# hub_board.net
KiCad netlist of a schematic drawn in EAGLE
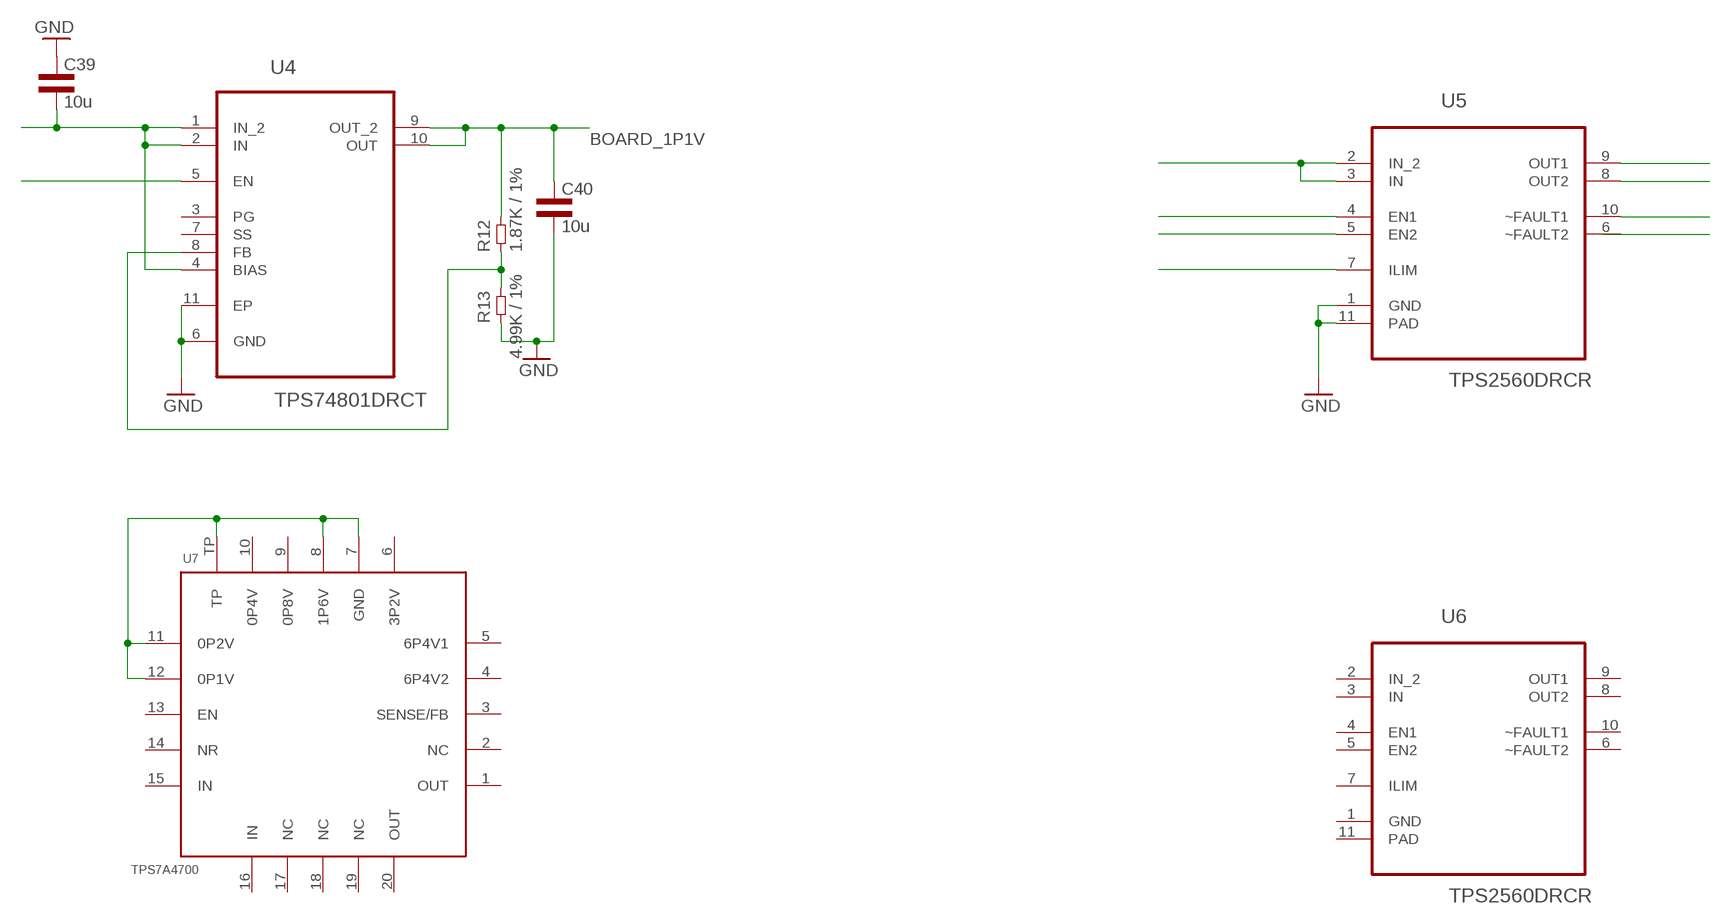
[diagram p0: schematic, sheet 1]
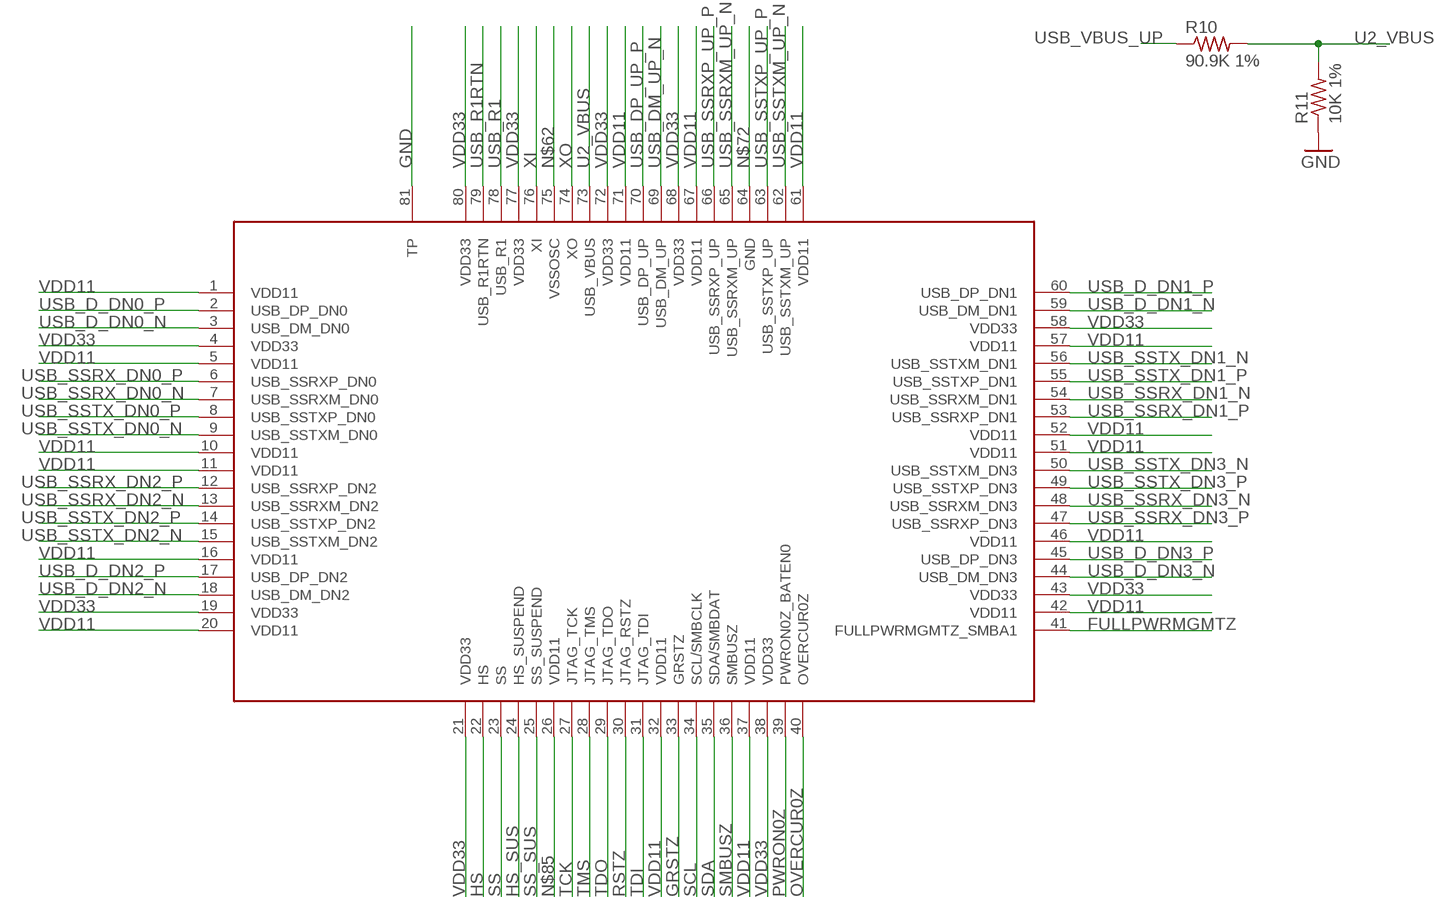
[diagram p1: schematic, sheet 2]
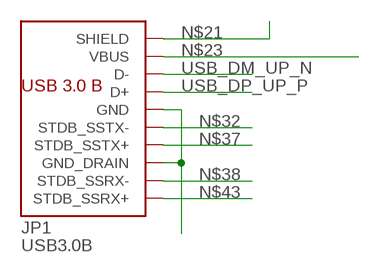
[diagram p2: schematic, sheet 3]
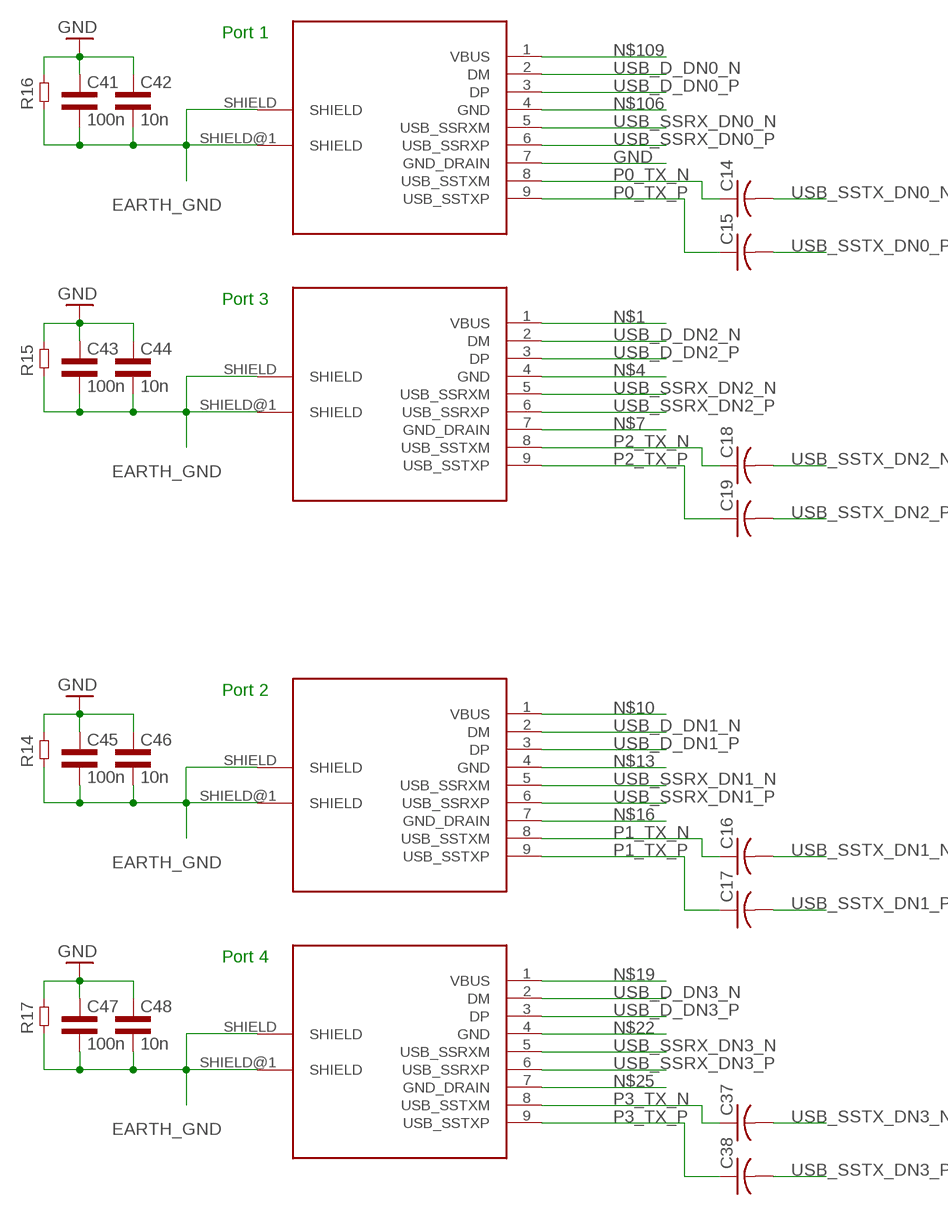
[diagram p3: schematic, sheet 4]
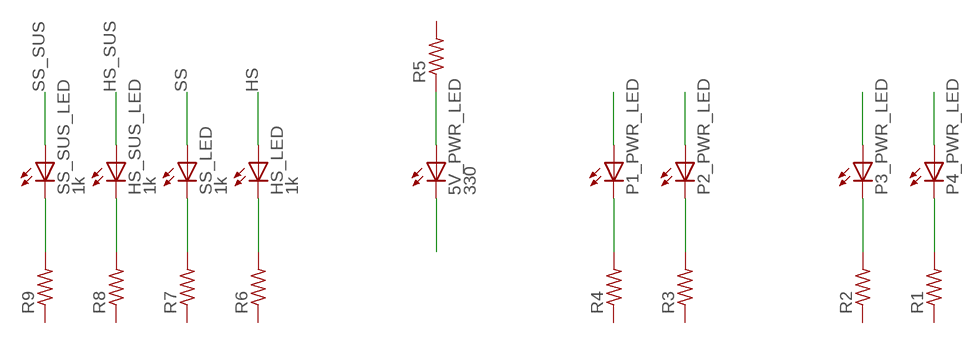
[diagram p4: schematic, sheet 5]
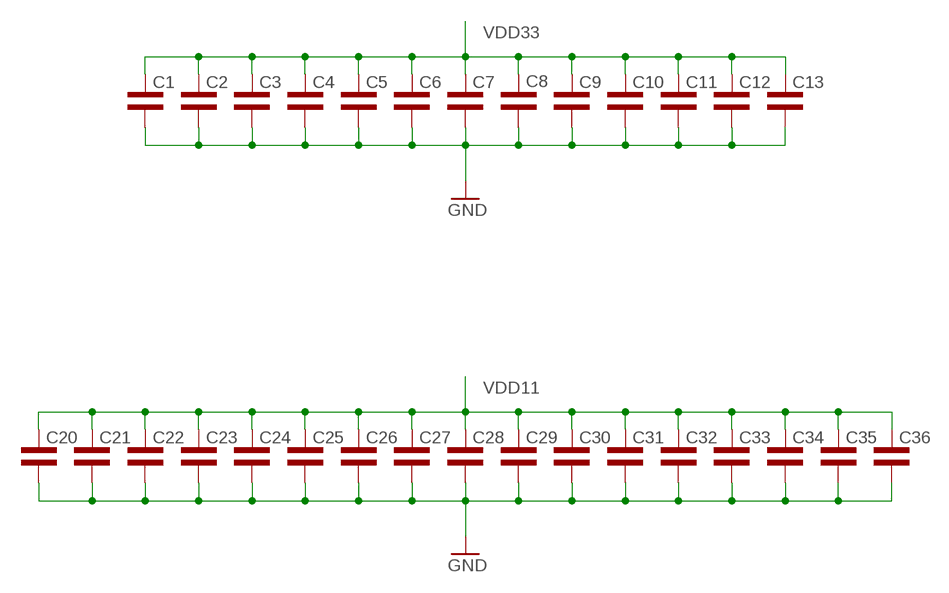
[diagram p5: schematic, sheet 6]

(export (version "E")
  (design (tool "Eeschema 10.0.6"))
  (components
    (comp (ref "C1")
      (value "CAP0402L3")
      (footprint "eagle-import:0402L3")
      (libsource (lib "eagle-import") (part "CAP0402L3"))
    )
    (comp (ref "C2")
      (value "CAP0402L3")
      (footprint "eagle-import:0402L3")
      (libsource (lib "eagle-import") (part "CAP0402L3"))
    )
    (comp (ref "C3")
      (value "CAP0402L3")
      (footprint "eagle-import:0402L3")
      (libsource (lib "eagle-import") (part "CAP0402L3"))
    )
    (comp (ref "C4")
      (value "CAP0402L3")
      (footprint "eagle-import:0402L3")
      (libsource (lib "eagle-import") (part "CAP0402L3"))
    )
    (comp (ref "C5")
      (value "CAP0402L3")
      (footprint "eagle-import:0402L3")
      (libsource (lib "eagle-import") (part "CAP0402L3"))
    )
    (comp (ref "C6")
      (value "CAP0402L3")
      (footprint "eagle-import:0402L3")
      (libsource (lib "eagle-import") (part "CAP0402L3"))
    )
    (comp (ref "C7")
      (value "CAP0402L3")
      (footprint "eagle-import:0402L3")
      (libsource (lib "eagle-import") (part "CAP0402L3"))
    )
    (comp (ref "C8")
      (value "CAP0402L3")
      (footprint "eagle-import:0402L3")
      (libsource (lib "eagle-import") (part "CAP0402L3"))
    )
    (comp (ref "C9")
      (value "CAP0402L3")
      (footprint "eagle-import:0402L3")
      (libsource (lib "eagle-import") (part "CAP0402L3"))
    )
    (comp (ref "C10")
      (value "CAP0402L3")
      (footprint "eagle-import:0402L3")
      (libsource (lib "eagle-import") (part "CAP0402L3"))
    )
    (comp (ref "C11")
      (value "CAP0402L3")
      (footprint "eagle-import:0402L3")
      (libsource (lib "eagle-import") (part "CAP0402L3"))
    )
    (comp (ref "C12")
      (value "CAP0402L3")
      (footprint "eagle-import:0402L3")
      (libsource (lib "eagle-import") (part "CAP0402L3"))
    )
    (comp (ref "C13")
      (value "CAP0402L3")
      (footprint "eagle-import:0402L3")
      (libsource (lib "eagle-import") (part "CAP0402L3"))
    )
    (comp (ref "C20")
      (value "CAP0402L3")
      (footprint "eagle-import:0402L3")
      (libsource (lib "eagle-import") (part "CAP0402L3"))
    )
    (comp (ref "C21")
      (value "CAP0402L3")
      (footprint "eagle-import:0402L3")
      (libsource (lib "eagle-import") (part "CAP0402L3"))
    )
    (comp (ref "C22")
      (value "CAP0402L3")
      (footprint "eagle-import:0402L3")
      (libsource (lib "eagle-import") (part "CAP0402L3"))
    )
    (comp (ref "C23")
      (value "CAP0402L3")
      (footprint "eagle-import:0402L3")
      (libsource (lib "eagle-import") (part "CAP0402L3"))
    )
    (comp (ref "C24")
      (value "CAP0402L3")
      (footprint "eagle-import:0402L3")
      (libsource (lib "eagle-import") (part "CAP0402L3"))
    )
    (comp (ref "C25")
      (value "CAP0402L3")
      (footprint "eagle-import:0402L3")
      (libsource (lib "eagle-import") (part "CAP0402L3"))
    )
    (comp (ref "C26")
      (value "CAP0402L3")
      (footprint "eagle-import:0402L3")
      (libsource (lib "eagle-import") (part "CAP0402L3"))
    )
    (comp (ref "C27")
      (value "CAP0402L3")
      (footprint "eagle-import:0402L3")
      (libsource (lib "eagle-import") (part "CAP0402L3"))
    )
    (comp (ref "C28")
      (value "CAP0402L3")
      (footprint "eagle-import:0402L3")
      (libsource (lib "eagle-import") (part "CAP0402L3"))
    )
    (comp (ref "C29")
      (value "CAP0402L3")
      (footprint "eagle-import:0402L3")
      (libsource (lib "eagle-import") (part "CAP0402L3"))
    )
    (comp (ref "C30")
      (value "CAP0402L3")
      (footprint "eagle-import:0402L3")
      (libsource (lib "eagle-import") (part "CAP0402L3"))
    )
    (comp (ref "C31")
      (value "CAP0402L3")
      (footprint "eagle-import:0402L3")
      (libsource (lib "eagle-import") (part "CAP0402L3"))
    )
    (comp (ref "C32")
      (value "CAP0402L3")
      (footprint "eagle-import:0402L3")
      (libsource (lib "eagle-import") (part "CAP0402L3"))
    )
    (comp (ref "C33")
      (value "CAP0402L3")
      (footprint "eagle-import:0402L3")
      (libsource (lib "eagle-import") (part "CAP0402L3"))
    )
    (comp (ref "C34")
      (value "CAP0402L3")
      (footprint "eagle-import:0402L3")
      (libsource (lib "eagle-import") (part "CAP0402L3"))
    )
    (comp (ref "C35")
      (value "CAP0402L3")
      (footprint "eagle-import:0402L3")
      (libsource (lib "eagle-import") (part "CAP0402L3"))
    )
    (comp (ref "C36")
      (value "CAP0402L3")
      (footprint "eagle-import:0402L3")
      (libsource (lib "eagle-import") (part "CAP0402L3"))
    )
    (comp (ref "JP1")
      (value "USB3.0B")
      (footprint "eagle-import:AMPHENOLUSB3.0B")
      (libsource (lib "eagle-import") (part "USB3.0B"))
    )
    (comp (ref "C39")
      (value "10u")
      (footprint "eagle-import:0805L3")
      (libsource (lib "eagle-import") (part "CAP0805L3"))
    )
    (comp (ref "C40")
      (value "10u")
      (footprint "eagle-import:0805L3")
      (libsource (lib "eagle-import") (part "CAP0805L3"))
    )
    (comp (ref "R12")
      (value "1.87K / 1%")
      (footprint "eagle-import:0603L3")
      (libsource (lib "eagle-import") (part "RES0603L3"))
    )
    (comp (ref "R13")
      (value "4.99K / 1%")
      (footprint "eagle-import:0603L3")
      (libsource (lib "eagle-import") (part "RES0603L3"))
    )
    (comp (ref "U4")
      (value "TPS74801DRCT")
      (footprint "eagle-import:SON50P300X300X100-11N")
      (libsource (lib "eagle-import") (part "TPS74801DRCT"))
    )
    (comp (ref "U5")
      (value "TPS2560DRCR")
      (footprint "eagle-import:SON50P300X300X100-11N")
      (libsource (lib "eagle-import") (part "TPS2560DRCR"))
    )
    (comp (ref "U6")
      (value "TPS2560DRCR")
      (footprint "eagle-import:SON50P300X300X100-11N")
      (libsource (lib "eagle-import") (part "TPS2560DRCR"))
    )
    (comp (ref "U7")
      (value "TPS7A4700")
      (footprint "eagle-import:VQFN-20")
      (libsource (lib "eagle-import") (part "TPS7A4700"))
    )
    (comp (ref "5V_PWR_LED")
      (value "330")
      (footprint "eagle-import:CHIP-LED0603")
      (libsource (lib "eagle-import") (part "LEDCHIP-LED0603"))
    )
    (comp (ref "HS_LED")
      (value "1k")
      (footprint "eagle-import:CHIP-LED0603")
      (libsource (lib "eagle-import") (part "LEDCHIP-LED0603"))
    )
    (comp (ref "HS_SUS_LED")
      (value "1k")
      (footprint "eagle-import:CHIP-LED0603")
      (libsource (lib "eagle-import") (part "LEDCHIP-LED0603"))
    )
    (comp (ref "P1_PWR_LED")
      (value "LEDCHIP-LED0603")
      (footprint "eagle-import:CHIP-LED0603")
      (libsource (lib "eagle-import") (part "LEDCHIP-LED0603"))
    )
    (comp (ref "P2_PWR_LED")
      (value "LEDCHIP-LED0603")
      (footprint "eagle-import:CHIP-LED0603")
      (libsource (lib "eagle-import") (part "LEDCHIP-LED0603"))
    )
    (comp (ref "P3_PWR_LED")
      (value "LEDCHIP-LED0603")
      (footprint "eagle-import:CHIP-LED0603")
      (libsource (lib "eagle-import") (part "LEDCHIP-LED0603"))
    )
    (comp (ref "P4_PWR_LED")
      (value "LEDCHIP-LED0603")
      (footprint "eagle-import:CHIP-LED0603")
      (libsource (lib "eagle-import") (part "LEDCHIP-LED0603"))
    )
    (comp (ref "R1")
      (value "R-US_R0603")
      (footprint "eagle-import:R0603")
      (libsource (lib "eagle-import") (part "R-US_R0603"))
    )
    (comp (ref "R2")
      (value "R-US_R0603")
      (footprint "eagle-import:R0603")
      (libsource (lib "eagle-import") (part "R-US_R0603"))
    )
    (comp (ref "R3")
      (value "R-US_R0603")
      (footprint "eagle-import:R0603")
      (libsource (lib "eagle-import") (part "R-US_R0603"))
    )
    (comp (ref "R4")
      (value "R-US_R0603")
      (footprint "eagle-import:R0603")
      (libsource (lib "eagle-import") (part "R-US_R0603"))
    )
    (comp (ref "R5")
      (value "R-US_R0603")
      (footprint "eagle-import:R0603")
      (libsource (lib "eagle-import") (part "R-US_R0603"))
    )
    (comp (ref "R6")
      (value "R-US_R0603")
      (footprint "eagle-import:R0603")
      (libsource (lib "eagle-import") (part "R-US_R0603"))
    )
    (comp (ref "R7")
      (value "R-US_R0603")
      (footprint "eagle-import:R0603")
      (libsource (lib "eagle-import") (part "R-US_R0603"))
    )
    (comp (ref "R8")
      (value "R-US_R0603")
      (footprint "eagle-import:R0603")
      (libsource (lib "eagle-import") (part "R-US_R0603"))
    )
    (comp (ref "R9")
      (value "R-US_R0603")
      (footprint "eagle-import:R0603")
      (libsource (lib "eagle-import") (part "R-US_R0603"))
    )
    (comp (ref "SS_LED")
      (value "1k")
      (footprint "eagle-import:CHIP-LED0603")
      (libsource (lib "eagle-import") (part "LEDCHIP-LED0603"))
    )
    (comp (ref "SS_SUS_LED")
      (value "1k")
      (footprint "eagle-import:CHIP-LED0603")
      (libsource (lib "eagle-import") (part "LEDCHIP-LED0603"))
    )
    (comp (ref "R10")
      (value "90.9K 1%")
      (footprint "eagle-import:R0603")
      (libsource (lib "eagle-import") (part "R-US_R0603"))
    )
    (comp (ref "R11")
      (value "10K 1%")
      (footprint "eagle-import:R0603")
      (libsource (lib "eagle-import") (part "R-US_R0603"))
    )
    (comp (ref "U2")
      (value "TUSB8040PFP")
      (footprint "eagle-import:S-PQFP-G80")
      (libsource (lib "eagle-import") (part "TUSB8040PFP"))
    )
    (comp (ref "C14")
      (value "C-USC0201")
      (footprint "eagle-import:C0201")
      (libsource (lib "eagle-import") (part "C-USC0201"))
    )
    (comp (ref "C15")
      (value "C-USC0201")
      (footprint "eagle-import:C0201")
      (libsource (lib "eagle-import") (part "C-USC0201"))
    )
    (comp (ref "C16")
      (value "C-USC0201")
      (footprint "eagle-import:C0201")
      (libsource (lib "eagle-import") (part "C-USC0201"))
    )
    (comp (ref "C17")
      (value "C-USC0201")
      (footprint "eagle-import:C0201")
      (libsource (lib "eagle-import") (part "C-USC0201"))
    )
    (comp (ref "C18")
      (value "C-USC0201")
      (footprint "eagle-import:C0201")
      (libsource (lib "eagle-import") (part "C-USC0201"))
    )
    (comp (ref "C19")
      (value "C-USC0201")
      (footprint "eagle-import:C0201")
      (libsource (lib "eagle-import") (part "C-USC0201"))
    )
    (comp (ref "C37")
      (value "C-USC0201")
      (footprint "eagle-import:C0201")
      (libsource (lib "eagle-import") (part "C-USC0201"))
    )
    (comp (ref "C38")
      (value "C-USC0201")
      (footprint "eagle-import:C0201")
      (libsource (lib "eagle-import") (part "C-USC0201"))
    )
    (comp (ref "C41")
      (value "100n")
      (footprint "eagle-import:0603L3")
      (libsource (lib "eagle-import") (part "CAP0603L3"))
    )
    (comp (ref "C42")
      (value "10n")
      (footprint "eagle-import:0603L3")
      (libsource (lib "eagle-import") (part "CAP0603L3"))
    )
    (comp (ref "C43")
      (value "100n")
      (footprint "eagle-import:0603L3")
      (libsource (lib "eagle-import") (part "CAP0603L3"))
    )
    (comp (ref "C44")
      (value "10n")
      (footprint "eagle-import:0603L3")
      (libsource (lib "eagle-import") (part "CAP0603L3"))
    )
    (comp (ref "C45")
      (value "100n")
      (footprint "eagle-import:0603L3")
      (libsource (lib "eagle-import") (part "CAP0603L3"))
    )
    (comp (ref "C46")
      (value "10n")
      (footprint "eagle-import:0603L3")
      (libsource (lib "eagle-import") (part "CAP0603L3"))
    )
    (comp (ref "C47")
      (value "100n")
      (footprint "eagle-import:0603L3")
      (libsource (lib "eagle-import") (part "CAP0603L3"))
    )
    (comp (ref "C48")
      (value "10n")
      (footprint "eagle-import:0603L3")
      (libsource (lib "eagle-import") (part "CAP0603L3"))
    )
    (comp (ref "R14")
      (value "RES0603L3")
      (footprint "eagle-import:0603L3")
      (libsource (lib "eagle-import") (part "RES0603L3"))
    )
    (comp (ref "R15")
      (value "RES0603L3")
      (footprint "eagle-import:0603L3")
      (libsource (lib "eagle-import") (part "RES0603L3"))
    )
    (comp (ref "R16")
      (value "RES0603L3")
      (footprint "eagle-import:0603L3")
      (libsource (lib "eagle-import") (part "RES0603L3"))
    )
    (comp (ref "R17")
      (value "RES0603L3")
      (footprint "eagle-import:0603L3")
      (libsource (lib "eagle-import") (part "RES0603L3"))
    )
    (comp (ref "U$1")
      (value "USB_SS_CONN_TYPE_A")
      (footprint "eagle-import:R_A_DIP")
      (libsource (lib "eagle-import") (part "USB_SS_CONN_TYPE_A"))
    )
    (comp (ref "U$3")
      (value "USB_SS_CONN_TYPE_A")
      (footprint "eagle-import:R_A_DIP")
      (libsource (lib "eagle-import") (part "USB_SS_CONN_TYPE_A"))
    )
    (comp (ref "U$4")
      (value "USB_SS_CONN_TYPE_A")
      (footprint "eagle-import:R_A_DIP")
      (libsource (lib "eagle-import") (part "USB_SS_CONN_TYPE_A"))
    )
    (comp (ref "U$5")
      (value "USB_SS_CONN_TYPE_A")
      (footprint "eagle-import:R_A_DIP")
      (libsource (lib "eagle-import") (part "USB_SS_CONN_TYPE_A"))
    )
  )
  (nets
    (net (code "1") (name "BOARD_1P1V") (class "Default")
      (node (ref "C40") (pin "1") (pinfunction "1_1") (pintype "bidirectional"))
      (node (ref "R12") (pin "P$2") (pinfunction "2_P$2") (pintype "bidirectional"))
      (node (ref "U4") (pin "10") (pinfunction "OUT_10") (pintype "output"))
      (node (ref "U4") (pin "9") (pinfunction "OUT_2_9") (pintype "output"))
    )
    (net (code "2") (name "EARTH_GND") (class "Default")
      (node (ref "C41") (pin "P$2") (pinfunction "2_P$2") (pintype "bidirectional"))
      (node (ref "C42") (pin "P$2") (pinfunction "2_P$2") (pintype "bidirectional"))
      (node (ref "C43") (pin "P$2") (pinfunction "2_P$2") (pintype "bidirectional"))
      (node (ref "C44") (pin "P$2") (pinfunction "2_P$2") (pintype "bidirectional"))
      (node (ref "C45") (pin "P$2") (pinfunction "2_P$2") (pintype "bidirectional"))
      (node (ref "C46") (pin "P$2") (pinfunction "2_P$2") (pintype "bidirectional"))
      (node (ref "C47") (pin "P$2") (pinfunction "2_P$2") (pintype "bidirectional"))
      (node (ref "C48") (pin "P$2") (pinfunction "2_P$2") (pintype "bidirectional"))
      (node (ref "R14") (pin "P$1") (pinfunction "1_P$1") (pintype "bidirectional"))
      (node (ref "R15") (pin "P$1") (pinfunction "1_P$1") (pintype "bidirectional"))
      (node (ref "R16") (pin "P$1") (pinfunction "1_P$1") (pintype "bidirectional"))
      (node (ref "R17") (pin "P$1") (pinfunction "1_P$1") (pintype "bidirectional"))
      (node (ref "U$1") (pin "SHIELD") (pinfunction "SHIELD_SHIELD") (pintype "bidirectional"))
      (node (ref "U$1") (pin "SHIELD@1") (pinfunction "SHIELD_SHIELD@1") (pintype "bidirectional"))
      (node (ref "U$3") (pin "SHIELD") (pinfunction "SHIELD_SHIELD") (pintype "bidirectional"))
      (node (ref "U$3") (pin "SHIELD@1") (pinfunction "SHIELD_SHIELD@1") (pintype "bidirectional"))
      (node (ref "U$4") (pin "SHIELD") (pinfunction "SHIELD_SHIELD") (pintype "bidirectional"))
      (node (ref "U$4") (pin "SHIELD@1") (pinfunction "SHIELD_SHIELD@1") (pintype "bidirectional"))
      (node (ref "U$5") (pin "SHIELD") (pinfunction "SHIELD_SHIELD") (pintype "bidirectional"))
      (node (ref "U$5") (pin "SHIELD@1") (pinfunction "SHIELD_SHIELD@1") (pintype "bidirectional"))
    )
    (net (code "3") (name "FULLPWRMGMTZ") (class "Default")
      (node (ref "U2") (pin "41") (pinfunction "FULLPWRMGMTZ_SMBA1_41") (pintype "bidirectional"))
    )
    (net (code "4") (name "GND") (class "Default")
      (node (ref "C1") (pin "P$2") (pinfunction "2_P$2") (pintype "bidirectional"))
      (node (ref "C10") (pin "P$2") (pinfunction "2_P$2") (pintype "bidirectional"))
      (node (ref "C11") (pin "P$2") (pinfunction "2_P$2") (pintype "bidirectional"))
      (node (ref "C12") (pin "P$2") (pinfunction "2_P$2") (pintype "bidirectional"))
      (node (ref "C13") (pin "P$2") (pinfunction "2_P$2") (pintype "bidirectional"))
      (node (ref "C2") (pin "P$2") (pinfunction "2_P$2") (pintype "bidirectional"))
      (node (ref "C20") (pin "P$2") (pinfunction "2_P$2") (pintype "bidirectional"))
      (node (ref "C21") (pin "P$2") (pinfunction "2_P$2") (pintype "bidirectional"))
      (node (ref "C22") (pin "P$2") (pinfunction "2_P$2") (pintype "bidirectional"))
      (node (ref "C23") (pin "P$2") (pinfunction "2_P$2") (pintype "bidirectional"))
      (node (ref "C24") (pin "P$2") (pinfunction "2_P$2") (pintype "bidirectional"))
      (node (ref "C25") (pin "P$2") (pinfunction "2_P$2") (pintype "bidirectional"))
      (node (ref "C26") (pin "P$2") (pinfunction "2_P$2") (pintype "bidirectional"))
      (node (ref "C27") (pin "P$2") (pinfunction "2_P$2") (pintype "bidirectional"))
      (node (ref "C28") (pin "P$2") (pinfunction "2_P$2") (pintype "bidirectional"))
      (node (ref "C29") (pin "P$2") (pinfunction "2_P$2") (pintype "bidirectional"))
      (node (ref "C3") (pin "P$2") (pinfunction "2_P$2") (pintype "bidirectional"))
      (node (ref "C30") (pin "P$2") (pinfunction "2_P$2") (pintype "bidirectional"))
      (node (ref "C31") (pin "P$2") (pinfunction "2_P$2") (pintype "bidirectional"))
      (node (ref "C32") (pin "P$2") (pinfunction "2_P$2") (pintype "bidirectional"))
      (node (ref "C33") (pin "P$2") (pinfunction "2_P$2") (pintype "bidirectional"))
      (node (ref "C34") (pin "P$2") (pinfunction "2_P$2") (pintype "bidirectional"))
      (node (ref "C35") (pin "P$2") (pinfunction "2_P$2") (pintype "bidirectional"))
      (node (ref "C36") (pin "P$2") (pinfunction "2_P$2") (pintype "bidirectional"))
      (node (ref "C39") (pin "1") (pinfunction "1_1") (pintype "bidirectional"))
      (node (ref "C4") (pin "P$2") (pinfunction "2_P$2") (pintype "bidirectional"))
      (node (ref "C40") (pin "2") (pinfunction "2_2") (pintype "bidirectional"))
      (node (ref "C41") (pin "P$1") (pinfunction "1_P$1") (pintype "bidirectional"))
      (node (ref "C42") (pin "P$1") (pinfunction "1_P$1") (pintype "bidirectional"))
      (node (ref "C43") (pin "P$1") (pinfunction "1_P$1") (pintype "bidirectional"))
      (node (ref "C44") (pin "P$1") (pinfunction "1_P$1") (pintype "bidirectional"))
      (node (ref "C45") (pin "P$1") (pinfunction "1_P$1") (pintype "bidirectional"))
      (node (ref "C46") (pin "P$1") (pinfunction "1_P$1") (pintype "bidirectional"))
      (node (ref "C47") (pin "P$1") (pinfunction "1_P$1") (pintype "bidirectional"))
      (node (ref "C48") (pin "P$1") (pinfunction "1_P$1") (pintype "bidirectional"))
      (node (ref "C5") (pin "P$2") (pinfunction "2_P$2") (pintype "bidirectional"))
      (node (ref "C6") (pin "P$2") (pinfunction "2_P$2") (pintype "bidirectional"))
      (node (ref "C7") (pin "P$2") (pinfunction "2_P$2") (pintype "bidirectional"))
      (node (ref "C8") (pin "P$2") (pinfunction "2_P$2") (pintype "bidirectional"))
      (node (ref "C9") (pin "P$2") (pinfunction "2_P$2") (pintype "bidirectional"))
      (node (ref "R11") (pin "1") (pinfunction "1_1") (pintype "passive"))
      (node (ref "R13") (pin "P$1") (pinfunction "1_P$1") (pintype "bidirectional"))
      (node (ref "R14") (pin "P$2") (pinfunction "2_P$2") (pintype "bidirectional"))
      (node (ref "R15") (pin "P$2") (pinfunction "2_P$2") (pintype "bidirectional"))
      (node (ref "R16") (pin "P$2") (pinfunction "2_P$2") (pintype "bidirectional"))
      (node (ref "R17") (pin "P$2") (pinfunction "2_P$2") (pintype "bidirectional"))
      (node (ref "U$1") (pin "7") (pinfunction "GND_DRAIN_7") (pintype "bidirectional"))
      (node (ref "U2") (pin "81") (pinfunction "TP_81") (pintype "bidirectional"))
      (node (ref "U4") (pin "11") (pinfunction "EP_11") (pintype "passive"))
      (node (ref "U4") (pin "6") (pinfunction "GND_6") (pintype "passive"))
      (node (ref "U5") (pin "1") (pinfunction "GND_1") (pintype "passive"))
      (node (ref "U5") (pin "11") (pinfunction "PAD_11") (pintype "passive"))
    )
    (net (code "5") (name "GRSTZ") (class "Default")
      (node (ref "U2") (pin "33") (pinfunction "GRSTZ_33") (pintype "bidirectional"))
    )
    (net (code "6") (name "HS") (class "Default")
      (node (ref "HS_LED") (pin "A") (pinfunction "A_A") (pintype "passive"))
      (node (ref "U2") (pin "22") (pinfunction "HS_22") (pintype "bidirectional"))
    )
    (net (code "7") (name "HS_SUS") (class "Default")
      (node (ref "HS_SUS_LED") (pin "A") (pinfunction "A_A") (pintype "passive"))
      (node (ref "U2") (pin "24") (pinfunction "HS_SUSPEND_24") (pintype "bidirectional"))
    )
    (net (code "8") (name "IN") (class "Default")
      (node (ref "U6") (pin "3") (pinfunction "IN_3") (pintype "power_in"))
    )
    (net (code "9") (name "IN_2") (class "Default")
      (node (ref "U6") (pin "2") (pinfunction "IN_2_2") (pintype "power_in"))
    )
    (net (code "10") (name "N$1") (class "Default")
      (node (ref "U$3") (pin "1") (pinfunction "VBUS_1") (pintype "bidirectional"))
    )
    (net (code "11") (name "N$4") (class "Default")
      (node (ref "U$3") (pin "4") (pinfunction "GND_4") (pintype "bidirectional"))
    )
    (net (code "12") (name "N$7") (class "Default")
      (node (ref "U$3") (pin "7") (pinfunction "GND_DRAIN_7") (pintype "bidirectional"))
    )
    (net (code "13") (name "N$10") (class "Default")
      (node (ref "U$4") (pin "1") (pinfunction "VBUS_1") (pintype "bidirectional"))
    )
    (net (code "14") (name "N$13") (class "Default")
      (node (ref "U$4") (pin "4") (pinfunction "GND_4") (pintype "bidirectional"))
    )
    (net (code "15") (name "N$16") (class "Default")
      (node (ref "U$4") (pin "7") (pinfunction "GND_DRAIN_7") (pintype "bidirectional"))
    )
    (net (code "16") (name "N$19") (class "Default")
      (node (ref "U$5") (pin "1") (pinfunction "VBUS_1") (pintype "bidirectional"))
    )
    (net (code "17") (name "N$21") (class "Default")
      (node (ref "JP1") (pin "10@1") (pinfunction "SHIELD_10@1") (pintype "bidirectional"))
      (node (ref "JP1") (pin "10@2") (pinfunction "SHIELD_10@2") (pintype "bidirectional"))
    )
    (net (code "18") (name "N$22") (class "Default")
      (node (ref "U$5") (pin "4") (pinfunction "GND_4") (pintype "bidirectional"))
    )
    (net (code "19") (name "N$23") (class "Default")
      (node (ref "JP1") (pin "1") (pinfunction "VBUS_1") (pintype "bidirectional"))
    )
    (net (code "20") (name "N$25") (class "Default")
      (node (ref "U$5") (pin "7") (pinfunction "GND_DRAIN_7") (pintype "bidirectional"))
    )
    (net (code "21") (name "N$32") (class "Default")
      (node (ref "JP1") (pin "5") (pinfunction "STDB_SSTX-_5") (pintype "bidirectional"))
    )
    (net (code "22") (name "N$37") (class "Default")
      (node (ref "JP1") (pin "6") (pinfunction "STDB_SSTX+_6") (pintype "bidirectional"))
    )
    (net (code "23") (name "N$38") (class "Default")
      (node (ref "JP1") (pin "8") (pinfunction "STDB_SSRX-_8") (pintype "bidirectional"))
    )
    (net (code "24") (name "N$43") (class "Default")
      (node (ref "JP1") (pin "9") (pinfunction "STDB_SSRX+_9") (pintype "bidirectional"))
    )
    (net (code "25") (name "N$62") (class "Default")
      (node (ref "U2") (pin "75") (pinfunction "VSSOSC_75") (pintype "bidirectional"))
    )
    (net (code "26") (name "N$72") (class "Default")
      (node (ref "U2") (pin "64") (pinfunction "GND_64") (pintype "bidirectional"))
    )
    (net (code "27") (name "N$85") (class "Default")
      (node (ref "U2") (pin "26") (pinfunction "VDD11_26") (pintype "bidirectional"))
    )
    (net (code "28") (name "N$106") (class "Default")
      (node (ref "U$1") (pin "4") (pinfunction "GND_4") (pintype "bidirectional"))
    )
    (net (code "29") (name "N$109") (class "Default")
      (node (ref "U$1") (pin "1") (pinfunction "VBUS_1") (pintype "bidirectional"))
    )
    (net (code "30") (name "Net-(5V_PWR_LED-PadA)") (class "Default")
      (node (ref "5V_PWR_LED") (pin "A") (pinfunction "A_A") (pintype "passive"))
      (node (ref "R5") (pin "1") (pinfunction "1_1") (pintype "passive"))
    )
    (net (code "31") (name "Net-(HS_LED-PadC)") (class "Default")
      (node (ref "HS_LED") (pin "C") (pinfunction "C_C") (pintype "passive"))
      (node (ref "R6") (pin "2") (pinfunction "2_2") (pintype "passive"))
    )
    (net (code "32") (name "Net-(HS_SUS_LED-PadC)") (class "Default")
      (node (ref "HS_SUS_LED") (pin "C") (pinfunction "C_C") (pintype "passive"))
      (node (ref "R8") (pin "2") (pinfunction "2_2") (pintype "passive"))
    )
    (net (code "33") (name "Net-(JP1-GND)") (class "Default")
      (node (ref "JP1") (pin "4") (pinfunction "GND_4") (pintype "bidirectional"))
      (node (ref "JP1") (pin "7") (pinfunction "GND_DRAIN_7") (pintype "bidirectional"))
    )
    (net (code "34") (name "Net-(P1_PWR_LED-PadC)") (class "Default")
      (node (ref "P1_PWR_LED") (pin "C") (pinfunction "C_C") (pintype "passive"))
      (node (ref "R4") (pin "2") (pinfunction "2_2") (pintype "passive"))
    )
    (net (code "35") (name "Net-(P2_PWR_LED-PadC)") (class "Default")
      (node (ref "P2_PWR_LED") (pin "C") (pinfunction "C_C") (pintype "passive"))
      (node (ref "R3") (pin "2") (pinfunction "2_2") (pintype "passive"))
    )
    (net (code "36") (name "Net-(P3_PWR_LED-PadC)") (class "Default")
      (node (ref "P3_PWR_LED") (pin "C") (pinfunction "C_C") (pintype "passive"))
      (node (ref "R2") (pin "2") (pinfunction "2_2") (pintype "passive"))
    )
    (net (code "37") (name "Net-(P4_PWR_LED-PadC)") (class "Default")
      (node (ref "P4_PWR_LED") (pin "C") (pinfunction "C_C") (pintype "passive"))
      (node (ref "R1") (pin "2") (pinfunction "2_2") (pintype "passive"))
    )
    (net (code "38") (name "Net-(R7-Pad2)") (class "Default")
      (node (ref "R7") (pin "2") (pinfunction "2_2") (pintype "passive"))
      (node (ref "SS_LED") (pin "C") (pinfunction "C_C") (pintype "passive"))
    )
    (net (code "39") (name "Net-(R9-Pad2)") (class "Default")
      (node (ref "R9") (pin "2") (pinfunction "2_2") (pintype "passive"))
      (node (ref "SS_SUS_LED") (pin "C") (pinfunction "C_C") (pintype "passive"))
    )
    (net (code "40") (name "Net-(R12-1)") (class "Default")
      (node (ref "R12") (pin "P$1") (pinfunction "1_P$1") (pintype "bidirectional"))
      (node (ref "R13") (pin "P$2") (pinfunction "2_P$2") (pintype "bidirectional"))
      (node (ref "U4") (pin "8") (pinfunction "FB_8") (pintype "passive"))
    )
    (net (code "41") (name "Net-(U4-BIAS)") (class "Default")
      (node (ref "C39") (pin "2") (pinfunction "2_2") (pintype "bidirectional"))
      (node (ref "U4") (pin "1") (pinfunction "IN_2_1") (pintype "input"))
      (node (ref "U4") (pin "2") (pinfunction "IN_2") (pintype "input"))
      (node (ref "U4") (pin "4") (pinfunction "BIAS_4") (pintype "input"))
    )
    (net (code "42") (name "Net-(U5-IN)") (class "Default")
      (node (ref "U5") (pin "2") (pinfunction "IN_2_2") (pintype "power_in"))
      (node (ref "U5") (pin "3") (pinfunction "IN_3") (pintype "power_in"))
    )
    (net (code "43") (name "Net-(U7-0P1V)") (class "Default")
      (node (ref "U7") (pin "11") (pinfunction "0P2V_11") (pintype "bidirectional"))
      (node (ref "U7") (pin "12") (pinfunction "0P1V_12") (pintype "bidirectional"))
      (node (ref "U7") (pin "7") (pinfunction "GND_7") (pintype "bidirectional"))
      (node (ref "U7") (pin "8") (pinfunction "1P6V_8") (pintype "bidirectional"))
      (node (ref "U7") (pin "TP") (pinfunction "TP_TP") (pintype "bidirectional"))
    )
    (net (code "44") (name "OVERCUR0Z") (class "Default")
      (node (ref "U2") (pin "40") (pinfunction "OVERCUR0Z_40") (pintype "bidirectional"))
    )
    (net (code "45") (name "P0_TX_N") (class "Default")
      (node (ref "C14") (pin "1") (pinfunction "1_1") (pintype "passive"))
      (node (ref "U$1") (pin "8") (pinfunction "USB_SSTXM_8") (pintype "bidirectional"))
    )
    (net (code "46") (name "P0_TX_P") (class "Default")
      (node (ref "C15") (pin "1") (pinfunction "1_1") (pintype "passive"))
      (node (ref "U$1") (pin "9") (pinfunction "USB_SSTXP_9") (pintype "bidirectional"))
    )
    (net (code "47") (name "P1_TX_N") (class "Default")
      (node (ref "C16") (pin "1") (pinfunction "1_1") (pintype "passive"))
      (node (ref "U$4") (pin "8") (pinfunction "USB_SSTXM_8") (pintype "bidirectional"))
    )
    (net (code "48") (name "P1_TX_P") (class "Default")
      (node (ref "C17") (pin "1") (pinfunction "1_1") (pintype "passive"))
      (node (ref "U$4") (pin "9") (pinfunction "USB_SSTXP_9") (pintype "bidirectional"))
    )
    (net (code "49") (name "P2_TX_N") (class "Default")
      (node (ref "C18") (pin "1") (pinfunction "1_1") (pintype "passive"))
      (node (ref "U$3") (pin "8") (pinfunction "USB_SSTXM_8") (pintype "bidirectional"))
    )
    (net (code "50") (name "P2_TX_P") (class "Default")
      (node (ref "C19") (pin "1") (pinfunction "1_1") (pintype "passive"))
      (node (ref "U$3") (pin "9") (pinfunction "USB_SSTXP_9") (pintype "bidirectional"))
    )
    (net (code "51") (name "P3_TX_N") (class "Default")
      (node (ref "C37") (pin "1") (pinfunction "1_1") (pintype "passive"))
      (node (ref "U$5") (pin "8") (pinfunction "USB_SSTXM_8") (pintype "bidirectional"))
    )
    (net (code "52") (name "P3_TX_P") (class "Default")
      (node (ref "C38") (pin "1") (pinfunction "1_1") (pintype "passive"))
      (node (ref "U$5") (pin "9") (pinfunction "USB_SSTXP_9") (pintype "bidirectional"))
    )
    (net (code "53") (name "PWRON0Z") (class "Default")
      (node (ref "U2") (pin "39") (pinfunction "PWRON0Z_BATEN0_39") (pintype "bidirectional"))
    )
    (net (code "54") (name "RSTZ") (class "Default")
      (node (ref "U2") (pin "30") (pinfunction "JTAG_RSTZ_30") (pintype "bidirectional"))
    )
    (net (code "55") (name "SCL") (class "Default")
      (node (ref "U2") (pin "34") (pinfunction "SCL/SMBCLK_34") (pintype "bidirectional"))
    )
    (net (code "56") (name "SDA") (class "Default")
      (node (ref "U2") (pin "35") (pinfunction "SDA/SMBDAT_35") (pintype "bidirectional"))
    )
    (net (code "57") (name "SMBUSZ") (class "Default")
      (node (ref "U2") (pin "36") (pinfunction "SMBUSZ_36") (pintype "bidirectional"))
    )
    (net (code "58") (name "SS") (class "Default")
      (node (ref "SS_LED") (pin "A") (pinfunction "A_A") (pintype "passive"))
      (node (ref "U2") (pin "23") (pinfunction "SS_23") (pintype "bidirectional"))
    )
    (net (code "59") (name "SS_SUS") (class "Default")
      (node (ref "SS_SUS_LED") (pin "A") (pinfunction "A_A") (pintype "passive"))
      (node (ref "U2") (pin "25") (pinfunction "SS_SUSPEND_25") (pintype "bidirectional"))
    )
    (net (code "60") (name "TCK") (class "Default")
      (node (ref "U2") (pin "27") (pinfunction "JTAG_TCK_27") (pintype "bidirectional"))
    )
    (net (code "61") (name "TDI") (class "Default")
      (node (ref "U2") (pin "31") (pinfunction "JTAG_TDI_31") (pintype "bidirectional"))
    )
    (net (code "62") (name "TDO") (class "Default")
      (node (ref "U2") (pin "29") (pinfunction "JTAG_TDO_29") (pintype "bidirectional"))
    )
    (net (code "63") (name "TMS") (class "Default")
      (node (ref "U2") (pin "28") (pinfunction "JTAG_TMS_28") (pintype "bidirectional"))
    )
    (net (code "64") (name "U2_VBUS") (class "Default")
      (node (ref "R10") (pin "2") (pinfunction "2_2") (pintype "passive"))
      (node (ref "R11") (pin "2") (pinfunction "2_2") (pintype "passive"))
      (node (ref "U2") (pin "73") (pinfunction "USB_VBUS_73") (pintype "bidirectional"))
    )
    (net (code "65") (name "USB_DM_UP_N") (class "Default")
      (node (ref "JP1") (pin "2") (pinfunction "D-_2") (pintype "bidirectional"))
      (node (ref "U2") (pin "69") (pinfunction "USB_DM_UP_69") (pintype "bidirectional"))
    )
    (net (code "66") (name "USB_DP_UP_P") (class "Default")
      (node (ref "JP1") (pin "3") (pinfunction "D+_3") (pintype "bidirectional"))
      (node (ref "U2") (pin "70") (pinfunction "USB_DP_UP_70") (pintype "bidirectional"))
    )
    (net (code "67") (name "USB_D_DN0_N") (class "Default")
      (node (ref "U$1") (pin "2") (pinfunction "DM_2") (pintype "bidirectional"))
      (node (ref "U2") (pin "3") (pinfunction "USB_DM_DN0_3") (pintype "bidirectional"))
    )
    (net (code "68") (name "USB_D_DN0_P") (class "Default")
      (node (ref "U$1") (pin "3") (pinfunction "DP_3") (pintype "bidirectional"))
      (node (ref "U2") (pin "2") (pinfunction "USB_DP_DN0_2") (pintype "bidirectional"))
    )
    (net (code "69") (name "USB_D_DN1_N") (class "Default")
      (node (ref "U$4") (pin "2") (pinfunction "DM_2") (pintype "bidirectional"))
      (node (ref "U2") (pin "59") (pinfunction "USB_DM_DN1_59") (pintype "bidirectional"))
    )
    (net (code "70") (name "USB_D_DN1_P") (class "Default")
      (node (ref "U$4") (pin "3") (pinfunction "DP_3") (pintype "bidirectional"))
      (node (ref "U2") (pin "60") (pinfunction "USB_DP_DN1_60") (pintype "bidirectional"))
    )
    (net (code "71") (name "USB_D_DN2_N") (class "Default")
      (node (ref "U$3") (pin "2") (pinfunction "DM_2") (pintype "bidirectional"))
      (node (ref "U2") (pin "18") (pinfunction "USB_DM_DN2_18") (pintype "bidirectional"))
    )
    (net (code "72") (name "USB_D_DN2_P") (class "Default")
      (node (ref "U$3") (pin "3") (pinfunction "DP_3") (pintype "bidirectional"))
      (node (ref "U2") (pin "17") (pinfunction "USB_DP_DN2_17") (pintype "bidirectional"))
    )
    (net (code "73") (name "USB_D_DN3_N") (class "Default")
      (node (ref "U$5") (pin "2") (pinfunction "DM_2") (pintype "bidirectional"))
      (node (ref "U2") (pin "44") (pinfunction "USB_DM_DN3_44") (pintype "bidirectional"))
    )
    (net (code "74") (name "USB_D_DN3_P") (class "Default")
      (node (ref "U$5") (pin "3") (pinfunction "DP_3") (pintype "bidirectional"))
      (node (ref "U2") (pin "45") (pinfunction "USB_DP_DN3_45") (pintype "bidirectional"))
    )
    (net (code "75") (name "USB_R1") (class "Default")
      (node (ref "U2") (pin "78") (pinfunction "USB_R1_78") (pintype "bidirectional"))
    )
    (net (code "76") (name "USB_R1RTN") (class "Default")
      (node (ref "U2") (pin "79") (pinfunction "USB_R1RTN_79") (pintype "bidirectional"))
    )
    (net (code "77") (name "USB_SSRXM_UP_N") (class "Default")
      (node (ref "U2") (pin "65") (pinfunction "USB_SSRXM_UP_65") (pintype "bidirectional"))
    )
    (net (code "78") (name "USB_SSRXP_UP_P") (class "Default")
      (node (ref "U2") (pin "66") (pinfunction "USB_SSRXP_UP_66") (pintype "bidirectional"))
    )
    (net (code "79") (name "USB_SSRX_DN0_N") (class "Default")
      (node (ref "U$1") (pin "5") (pinfunction "USB_SSRXM_5") (pintype "bidirectional"))
      (node (ref "U2") (pin "7") (pinfunction "USB_SSRXM_DN0_7") (pintype "bidirectional"))
    )
    (net (code "80") (name "USB_SSRX_DN0_P") (class "Default")
      (node (ref "U$1") (pin "6") (pinfunction "USB_SSRXP_6") (pintype "bidirectional"))
      (node (ref "U2") (pin "6") (pinfunction "USB_SSRXP_DN0_6") (pintype "bidirectional"))
    )
    (net (code "81") (name "USB_SSRX_DN1_N") (class "Default")
      (node (ref "U$4") (pin "5") (pinfunction "USB_SSRXM_5") (pintype "bidirectional"))
      (node (ref "U2") (pin "54") (pinfunction "USB_SSRXM_DN1_54") (pintype "bidirectional"))
    )
    (net (code "82") (name "USB_SSRX_DN1_P") (class "Default")
      (node (ref "U$4") (pin "6") (pinfunction "USB_SSRXP_6") (pintype "bidirectional"))
      (node (ref "U2") (pin "53") (pinfunction "USB_SSRXP_DN1_53") (pintype "bidirectional"))
    )
    (net (code "83") (name "USB_SSRX_DN2_N") (class "Default")
      (node (ref "U$3") (pin "5") (pinfunction "USB_SSRXM_5") (pintype "bidirectional"))
      (node (ref "U2") (pin "13") (pinfunction "USB_SSRXM_DN2_13") (pintype "bidirectional"))
    )
    (net (code "84") (name "USB_SSRX_DN2_P") (class "Default")
      (node (ref "U$3") (pin "6") (pinfunction "USB_SSRXP_6") (pintype "bidirectional"))
      (node (ref "U2") (pin "12") (pinfunction "USB_SSRXP_DN2_12") (pintype "bidirectional"))
    )
    (net (code "85") (name "USB_SSRX_DN3_N") (class "Default")
      (node (ref "U$5") (pin "5") (pinfunction "USB_SSRXM_5") (pintype "bidirectional"))
      (node (ref "U2") (pin "48") (pinfunction "USB_SSRXM_DN3_48") (pintype "bidirectional"))
    )
    (net (code "86") (name "USB_SSRX_DN3_P") (class "Default")
      (node (ref "U$5") (pin "6") (pinfunction "USB_SSRXP_6") (pintype "bidirectional"))
      (node (ref "U2") (pin "47") (pinfunction "USB_SSRXP_DN3_47") (pintype "bidirectional"))
    )
    (net (code "87") (name "USB_SSTXM_UP_N") (class "Default")
      (node (ref "U2") (pin "62") (pinfunction "USB_SSTXM_UP_62") (pintype "bidirectional"))
    )
    (net (code "88") (name "USB_SSTXP_UP_P") (class "Default")
      (node (ref "U2") (pin "63") (pinfunction "USB_SSTXP_UP_63") (pintype "bidirectional"))
    )
    (net (code "89") (name "USB_SSTX_DN0_N") (class "Default")
      (node (ref "C14") (pin "2") (pinfunction "2_2") (pintype "passive"))
      (node (ref "U2") (pin "9") (pinfunction "USB_SSTXM_DN0_9") (pintype "bidirectional"))
    )
    (net (code "90") (name "USB_SSTX_DN0_P") (class "Default")
      (node (ref "C15") (pin "2") (pinfunction "2_2") (pintype "passive"))
      (node (ref "U2") (pin "8") (pinfunction "USB_SSTXP_DN0_8") (pintype "bidirectional"))
    )
    (net (code "91") (name "USB_SSTX_DN1_N") (class "Default")
      (node (ref "C16") (pin "2") (pinfunction "2_2") (pintype "passive"))
      (node (ref "U2") (pin "56") (pinfunction "USB_SSTXM_DN1_56") (pintype "bidirectional"))
    )
    (net (code "92") (name "USB_SSTX_DN1_P") (class "Default")
      (node (ref "C17") (pin "2") (pinfunction "2_2") (pintype "passive"))
      (node (ref "U2") (pin "55") (pinfunction "USB_SSTXP_DN1_55") (pintype "bidirectional"))
    )
    (net (code "93") (name "USB_SSTX_DN2_N") (class "Default")
      (node (ref "C18") (pin "2") (pinfunction "2_2") (pintype "passive"))
      (node (ref "U2") (pin "15") (pinfunction "USB_SSTXM_DN2_15") (pintype "bidirectional"))
    )
    (net (code "94") (name "USB_SSTX_DN2_P") (class "Default")
      (node (ref "C19") (pin "2") (pinfunction "2_2") (pintype "passive"))
      (node (ref "U2") (pin "14") (pinfunction "USB_SSTXP_DN2_14") (pintype "bidirectional"))
    )
    (net (code "95") (name "USB_SSTX_DN3_N") (class "Default")
      (node (ref "C37") (pin "2") (pinfunction "2_2") (pintype "passive"))
      (node (ref "U2") (pin "50") (pinfunction "USB_SSTXM_DN3_50") (pintype "bidirectional"))
    )
    (net (code "96") (name "USB_SSTX_DN3_P") (class "Default")
      (node (ref "C38") (pin "2") (pinfunction "2_2") (pintype "passive"))
      (node (ref "U2") (pin "49") (pinfunction "USB_SSTXP_DN3_49") (pintype "bidirectional"))
    )
    (net (code "97") (name "USB_VBUS_UP") (class "Default")
      (node (ref "R10") (pin "1") (pinfunction "1_1") (pintype "passive"))
    )
    (net (code "98") (name "VDD11") (class "Default")
      (node (ref "C20") (pin "P$1") (pinfunction "1_P$1") (pintype "bidirectional"))
      (node (ref "C21") (pin "P$1") (pinfunction "1_P$1") (pintype "bidirectional"))
      (node (ref "C22") (pin "P$1") (pinfunction "1_P$1") (pintype "bidirectional"))
      (node (ref "C23") (pin "P$1") (pinfunction "1_P$1") (pintype "bidirectional"))
      (node (ref "C24") (pin "P$1") (pinfunction "1_P$1") (pintype "bidirectional"))
      (node (ref "C25") (pin "P$1") (pinfunction "1_P$1") (pintype "bidirectional"))
      (node (ref "C26") (pin "P$1") (pinfunction "1_P$1") (pintype "bidirectional"))
      (node (ref "C27") (pin "P$1") (pinfunction "1_P$1") (pintype "bidirectional"))
      (node (ref "C28") (pin "P$1") (pinfunction "1_P$1") (pintype "bidirectional"))
      (node (ref "C29") (pin "P$1") (pinfunction "1_P$1") (pintype "bidirectional"))
      (node (ref "C30") (pin "P$1") (pinfunction "1_P$1") (pintype "bidirectional"))
      (node (ref "C31") (pin "P$1") (pinfunction "1_P$1") (pintype "bidirectional"))
      (node (ref "C32") (pin "P$1") (pinfunction "1_P$1") (pintype "bidirectional"))
      (node (ref "C33") (pin "P$1") (pinfunction "1_P$1") (pintype "bidirectional"))
      (node (ref "C34") (pin "P$1") (pinfunction "1_P$1") (pintype "bidirectional"))
      (node (ref "C35") (pin "P$1") (pinfunction "1_P$1") (pintype "bidirectional"))
      (node (ref "C36") (pin "P$1") (pinfunction "1_P$1") (pintype "bidirectional"))
      (node (ref "U2") (pin "1") (pinfunction "VDD11_1") (pintype "bidirectional"))
      (node (ref "U2") (pin "10") (pinfunction "VDD11_10") (pintype "bidirectional"))
      (node (ref "U2") (pin "11") (pinfunction "VDD11_11") (pintype "bidirectional"))
      (node (ref "U2") (pin "16") (pinfunction "VDD11_16") (pintype "bidirectional"))
      (node (ref "U2") (pin "20") (pinfunction "VDD11_20") (pintype "bidirectional"))
      (node (ref "U2") (pin "32") (pinfunction "VDD11_32") (pintype "bidirectional"))
      (node (ref "U2") (pin "37") (pinfunction "VDD11_37") (pintype "bidirectional"))
      (node (ref "U2") (pin "42") (pinfunction "VDD11_42") (pintype "bidirectional"))
      (node (ref "U2") (pin "46") (pinfunction "VDD11_46") (pintype "bidirectional"))
      (node (ref "U2") (pin "5") (pinfunction "VDD11_5") (pintype "bidirectional"))
      (node (ref "U2") (pin "51") (pinfunction "VDD11_51") (pintype "bidirectional"))
      (node (ref "U2") (pin "52") (pinfunction "VDD11_52") (pintype "bidirectional"))
      (node (ref "U2") (pin "57") (pinfunction "VDD11_57") (pintype "bidirectional"))
      (node (ref "U2") (pin "61") (pinfunction "VDD11_61") (pintype "bidirectional"))
      (node (ref "U2") (pin "67") (pinfunction "VDD11_67") (pintype "bidirectional"))
      (node (ref "U2") (pin "71") (pinfunction "VDD11_71") (pintype "bidirectional"))
    )
    (net (code "99") (name "VDD33") (class "Default")
      (node (ref "C1") (pin "P$1") (pinfunction "1_P$1") (pintype "bidirectional"))
      (node (ref "C10") (pin "P$1") (pinfunction "1_P$1") (pintype "bidirectional"))
      (node (ref "C11") (pin "P$1") (pinfunction "1_P$1") (pintype "bidirectional"))
      (node (ref "C12") (pin "P$1") (pinfunction "1_P$1") (pintype "bidirectional"))
      (node (ref "C13") (pin "P$1") (pinfunction "1_P$1") (pintype "bidirectional"))
      (node (ref "C2") (pin "P$1") (pinfunction "1_P$1") (pintype "bidirectional"))
      (node (ref "C3") (pin "P$1") (pinfunction "1_P$1") (pintype "bidirectional"))
      (node (ref "C4") (pin "P$1") (pinfunction "1_P$1") (pintype "bidirectional"))
      (node (ref "C5") (pin "P$1") (pinfunction "1_P$1") (pintype "bidirectional"))
      (node (ref "C6") (pin "P$1") (pinfunction "1_P$1") (pintype "bidirectional"))
      (node (ref "C7") (pin "P$1") (pinfunction "1_P$1") (pintype "bidirectional"))
      (node (ref "C8") (pin "P$1") (pinfunction "1_P$1") (pintype "bidirectional"))
      (node (ref "C9") (pin "P$1") (pinfunction "1_P$1") (pintype "bidirectional"))
      (node (ref "U2") (pin "19") (pinfunction "VDD33_19") (pintype "bidirectional"))
      (node (ref "U2") (pin "21") (pinfunction "VDD33_21") (pintype "bidirectional"))
      (node (ref "U2") (pin "38") (pinfunction "VDD33_38") (pintype "bidirectional"))
      (node (ref "U2") (pin "4") (pinfunction "VDD33_4") (pintype "bidirectional"))
      (node (ref "U2") (pin "43") (pinfunction "VDD33_43") (pintype "bidirectional"))
      (node (ref "U2") (pin "58") (pinfunction "VDD33_58") (pintype "bidirectional"))
      (node (ref "U2") (pin "68") (pinfunction "VDD33_68") (pintype "bidirectional"))
      (node (ref "U2") (pin "72") (pinfunction "VDD33_72") (pintype "bidirectional"))
      (node (ref "U2") (pin "77") (pinfunction "VDD33_77") (pintype "bidirectional"))
      (node (ref "U2") (pin "80") (pinfunction "VDD33_80") (pintype "bidirectional"))
    )
    (net (code "100") (name "XI") (class "Default")
      (node (ref "U2") (pin "76") (pinfunction "XI_76") (pintype "bidirectional"))
    )
    (net (code "101") (name "XO") (class "Default")
      (node (ref "U2") (pin "74") (pinfunction "XO_74") (pintype "bidirectional"))
    )
    (net (code "102") (name "unconnected-(5V_PWR_LED-PadC)") (class "Default")
      (node (ref "5V_PWR_LED") (pin "C") (pinfunction "C_C") (pintype "passive"))
    )
    (net (code "103") (name "unconnected-(P1_PWR_LED-PadA)") (class "Default")
      (node (ref "P1_PWR_LED") (pin "A") (pinfunction "A_A") (pintype "passive"))
    )
    (net (code "104") (name "unconnected-(P2_PWR_LED-PadA)") (class "Default")
      (node (ref "P2_PWR_LED") (pin "A") (pinfunction "A_A") (pintype "passive"))
    )
    (net (code "105") (name "unconnected-(P3_PWR_LED-PadA)") (class "Default")
      (node (ref "P3_PWR_LED") (pin "A") (pinfunction "A_A") (pintype "passive"))
    )
    (net (code "106") (name "unconnected-(P4_PWR_LED-PadA)") (class "Default")
      (node (ref "P4_PWR_LED") (pin "A") (pinfunction "A_A") (pintype "passive"))
    )
    (net (code "107") (name "unconnected-(R1-Pad1)") (class "Default")
      (node (ref "R1") (pin "1") (pinfunction "1_1") (pintype "passive"))
    )
    (net (code "108") (name "unconnected-(R2-Pad1)") (class "Default")
      (node (ref "R2") (pin "1") (pinfunction "1_1") (pintype "passive"))
    )
    (net (code "109") (name "unconnected-(R3-Pad1)") (class "Default")
      (node (ref "R3") (pin "1") (pinfunction "1_1") (pintype "passive"))
    )
    (net (code "110") (name "unconnected-(R4-Pad1)") (class "Default")
      (node (ref "R4") (pin "1") (pinfunction "1_1") (pintype "passive"))
    )
    (net (code "111") (name "unconnected-(R5-Pad2)") (class "Default")
      (node (ref "R5") (pin "2") (pinfunction "2_2") (pintype "passive"))
    )
    (net (code "112") (name "unconnected-(R6-Pad1)") (class "Default")
      (node (ref "R6") (pin "1") (pinfunction "1_1") (pintype "passive"))
    )
    (net (code "113") (name "unconnected-(R7-Pad1)") (class "Default")
      (node (ref "R7") (pin "1") (pinfunction "1_1") (pintype "passive"))
    )
    (net (code "114") (name "unconnected-(R8-Pad1)") (class "Default")
      (node (ref "R8") (pin "1") (pinfunction "1_1") (pintype "passive"))
    )
    (net (code "115") (name "unconnected-(R9-Pad1)") (class "Default")
      (node (ref "R9") (pin "1") (pinfunction "1_1") (pintype "passive"))
    )
    (net (code "116") (name "unconnected-(U4-EN-Pad5)") (class "Default")
      (node (ref "U4") (pin "5") (pinfunction "EN_5") (pintype "input"))
    )
    (net (code "117") (name "unconnected-(U4-PG-Pad3)") (class "Default")
      (node (ref "U4") (pin "3") (pinfunction "PG_3") (pintype "output"))
    )
    (net (code "118") (name "unconnected-(U4-SS-Pad7)") (class "Default")
      (node (ref "U4") (pin "7") (pinfunction "SS_7") (pintype "input"))
    )
    (net (code "119") (name "unconnected-(U5-EN1-Pad4)") (class "Default")
      (node (ref "U5") (pin "4") (pinfunction "EN1_4") (pintype "input"))
    )
    (net (code "120") (name "unconnected-(U5-EN2-Pad5)") (class "Default")
      (node (ref "U5") (pin "5") (pinfunction "EN2_5") (pintype "input"))
    )
    (net (code "121") (name "unconnected-(U5-ILIM-Pad7)") (class "Default")
      (node (ref "U5") (pin "7") (pinfunction "ILIM_7") (pintype "passive"))
    )
    (net (code "122") (name "unconnected-(U5-OUT1-Pad9)") (class "Default")
      (node (ref "U5") (pin "9") (pinfunction "OUT1_9") (pintype "output"))
    )
    (net (code "123") (name "unconnected-(U5-OUT2-Pad8)") (class "Default")
      (node (ref "U5") (pin "8") (pinfunction "OUT2_8") (pintype "output"))
    )
    (net (code "124") (name "unconnected-(U5-~{FAULT1}-Pad10)") (class "Default")
      (node (ref "U5") (pin "10") (pinfunction "~{FAULT1}_10") (pintype "output"))
    )
    (net (code "125") (name "unconnected-(U5-~{FAULT2}-Pad6)") (class "Default")
      (node (ref "U5") (pin "6") (pinfunction "~{FAULT2}_6") (pintype "output"))
    )
    (net (code "126") (name "unconnected-(U6-EN1-Pad4)") (class "Default")
      (node (ref "U6") (pin "4") (pinfunction "EN1_4") (pintype "input"))
    )
    (net (code "127") (name "unconnected-(U6-EN2-Pad5)") (class "Default")
      (node (ref "U6") (pin "5") (pinfunction "EN2_5") (pintype "input"))
    )
    (net (code "128") (name "unconnected-(U6-GND-Pad1)") (class "Default")
      (node (ref "U6") (pin "1") (pinfunction "GND_1") (pintype "passive"))
    )
    (net (code "129") (name "unconnected-(U6-ILIM-Pad7)") (class "Default")
      (node (ref "U6") (pin "7") (pinfunction "ILIM_7") (pintype "passive"))
    )
    (net (code "130") (name "unconnected-(U6-OUT1-Pad9)") (class "Default")
      (node (ref "U6") (pin "9") (pinfunction "OUT1_9") (pintype "output"))
    )
    (net (code "131") (name "unconnected-(U6-OUT2-Pad8)") (class "Default")
      (node (ref "U6") (pin "8") (pinfunction "OUT2_8") (pintype "output"))
    )
    (net (code "132") (name "unconnected-(U6-PAD-Pad11)") (class "Default")
      (node (ref "U6") (pin "11") (pinfunction "PAD_11") (pintype "passive"))
    )
    (net (code "133") (name "unconnected-(U6-~{FAULT1}-Pad10)") (class "Default")
      (node (ref "U6") (pin "10") (pinfunction "~{FAULT1}_10") (pintype "output"))
    )
    (net (code "134") (name "unconnected-(U6-~{FAULT2}-Pad6)") (class "Default")
      (node (ref "U6") (pin "6") (pinfunction "~{FAULT2}_6") (pintype "output"))
    )
    (net (code "135") (name "unconnected-(U7-0P4V-Pad10)") (class "Default")
      (node (ref "U7") (pin "10") (pinfunction "0P4V_10") (pintype "bidirectional"))
    )
    (net (code "136") (name "unconnected-(U7-0P8V-Pad9)") (class "Default")
      (node (ref "U7") (pin "9") (pinfunction "0P8V_9") (pintype "bidirectional"))
    )
    (net (code "137") (name "unconnected-(U7-3P2V-Pad6)") (class "Default")
      (node (ref "U7") (pin "6") (pinfunction "3P2V_6") (pintype "bidirectional"))
    )
    (net (code "138") (name "unconnected-(U7-6P4V1-Pad5)") (class "Default")
      (node (ref "U7") (pin "5") (pinfunction "6P4V1_5") (pintype "bidirectional"))
    )
    (net (code "139") (name "unconnected-(U7-6P4V2-Pad4)") (class "Default")
      (node (ref "U7") (pin "4") (pinfunction "6P4V2_4") (pintype "bidirectional"))
    )
    (net (code "140") (name "unconnected-(U7-EN-Pad13)") (class "Default")
      (node (ref "U7") (pin "13") (pinfunction "EN_13") (pintype "bidirectional"))
    )
    (net (code "141") (name "unconnected-(U7-IN-Pad15)") (class "Default")
      (node (ref "U7") (pin "15") (pinfunction "IN_15") (pintype "bidirectional"))
    )
    (net (code "142") (name "unconnected-(U7-IN-Pad16)") (class "Default")
      (node (ref "U7") (pin "16") (pinfunction "IN_16") (pintype "bidirectional"))
    )
    (net (code "143") (name "unconnected-(U7-NC-Pad2)") (class "Default")
      (node (ref "U7") (pin "2") (pinfunction "NC_2") (pintype "bidirectional"))
    )
    (net (code "144") (name "unconnected-(U7-NC-Pad17)") (class "Default")
      (node (ref "U7") (pin "17") (pinfunction "NC_17") (pintype "bidirectional"))
    )
    (net (code "145") (name "unconnected-(U7-NC-Pad18)") (class "Default")
      (node (ref "U7") (pin "18") (pinfunction "NC_18") (pintype "bidirectional"))
    )
    (net (code "146") (name "unconnected-(U7-NC-Pad19)") (class "Default")
      (node (ref "U7") (pin "19") (pinfunction "NC_19") (pintype "bidirectional"))
    )
    (net (code "147") (name "unconnected-(U7-NR-Pad14)") (class "Default")
      (node (ref "U7") (pin "14") (pinfunction "NR_14") (pintype "bidirectional"))
    )
    (net (code "148") (name "unconnected-(U7-OUT-Pad1)") (class "Default")
      (node (ref "U7") (pin "1") (pinfunction "OUT_1") (pintype "bidirectional"))
    )
    (net (code "149") (name "unconnected-(U7-OUT-Pad20)") (class "Default")
      (node (ref "U7") (pin "20") (pinfunction "OUT_20") (pintype "bidirectional"))
    )
    (net (code "150") (name "unconnected-(U7-SENSE{slash}FB-Pad3)") (class "Default")
      (node (ref "U7") (pin "3") (pinfunction "SENSE/FB_3") (pintype "bidirectional"))
    )
  )
)
